# SCH_555-circuit_2025-10-19.net
KiCad netlist of a schematic drawn in EasyEDA
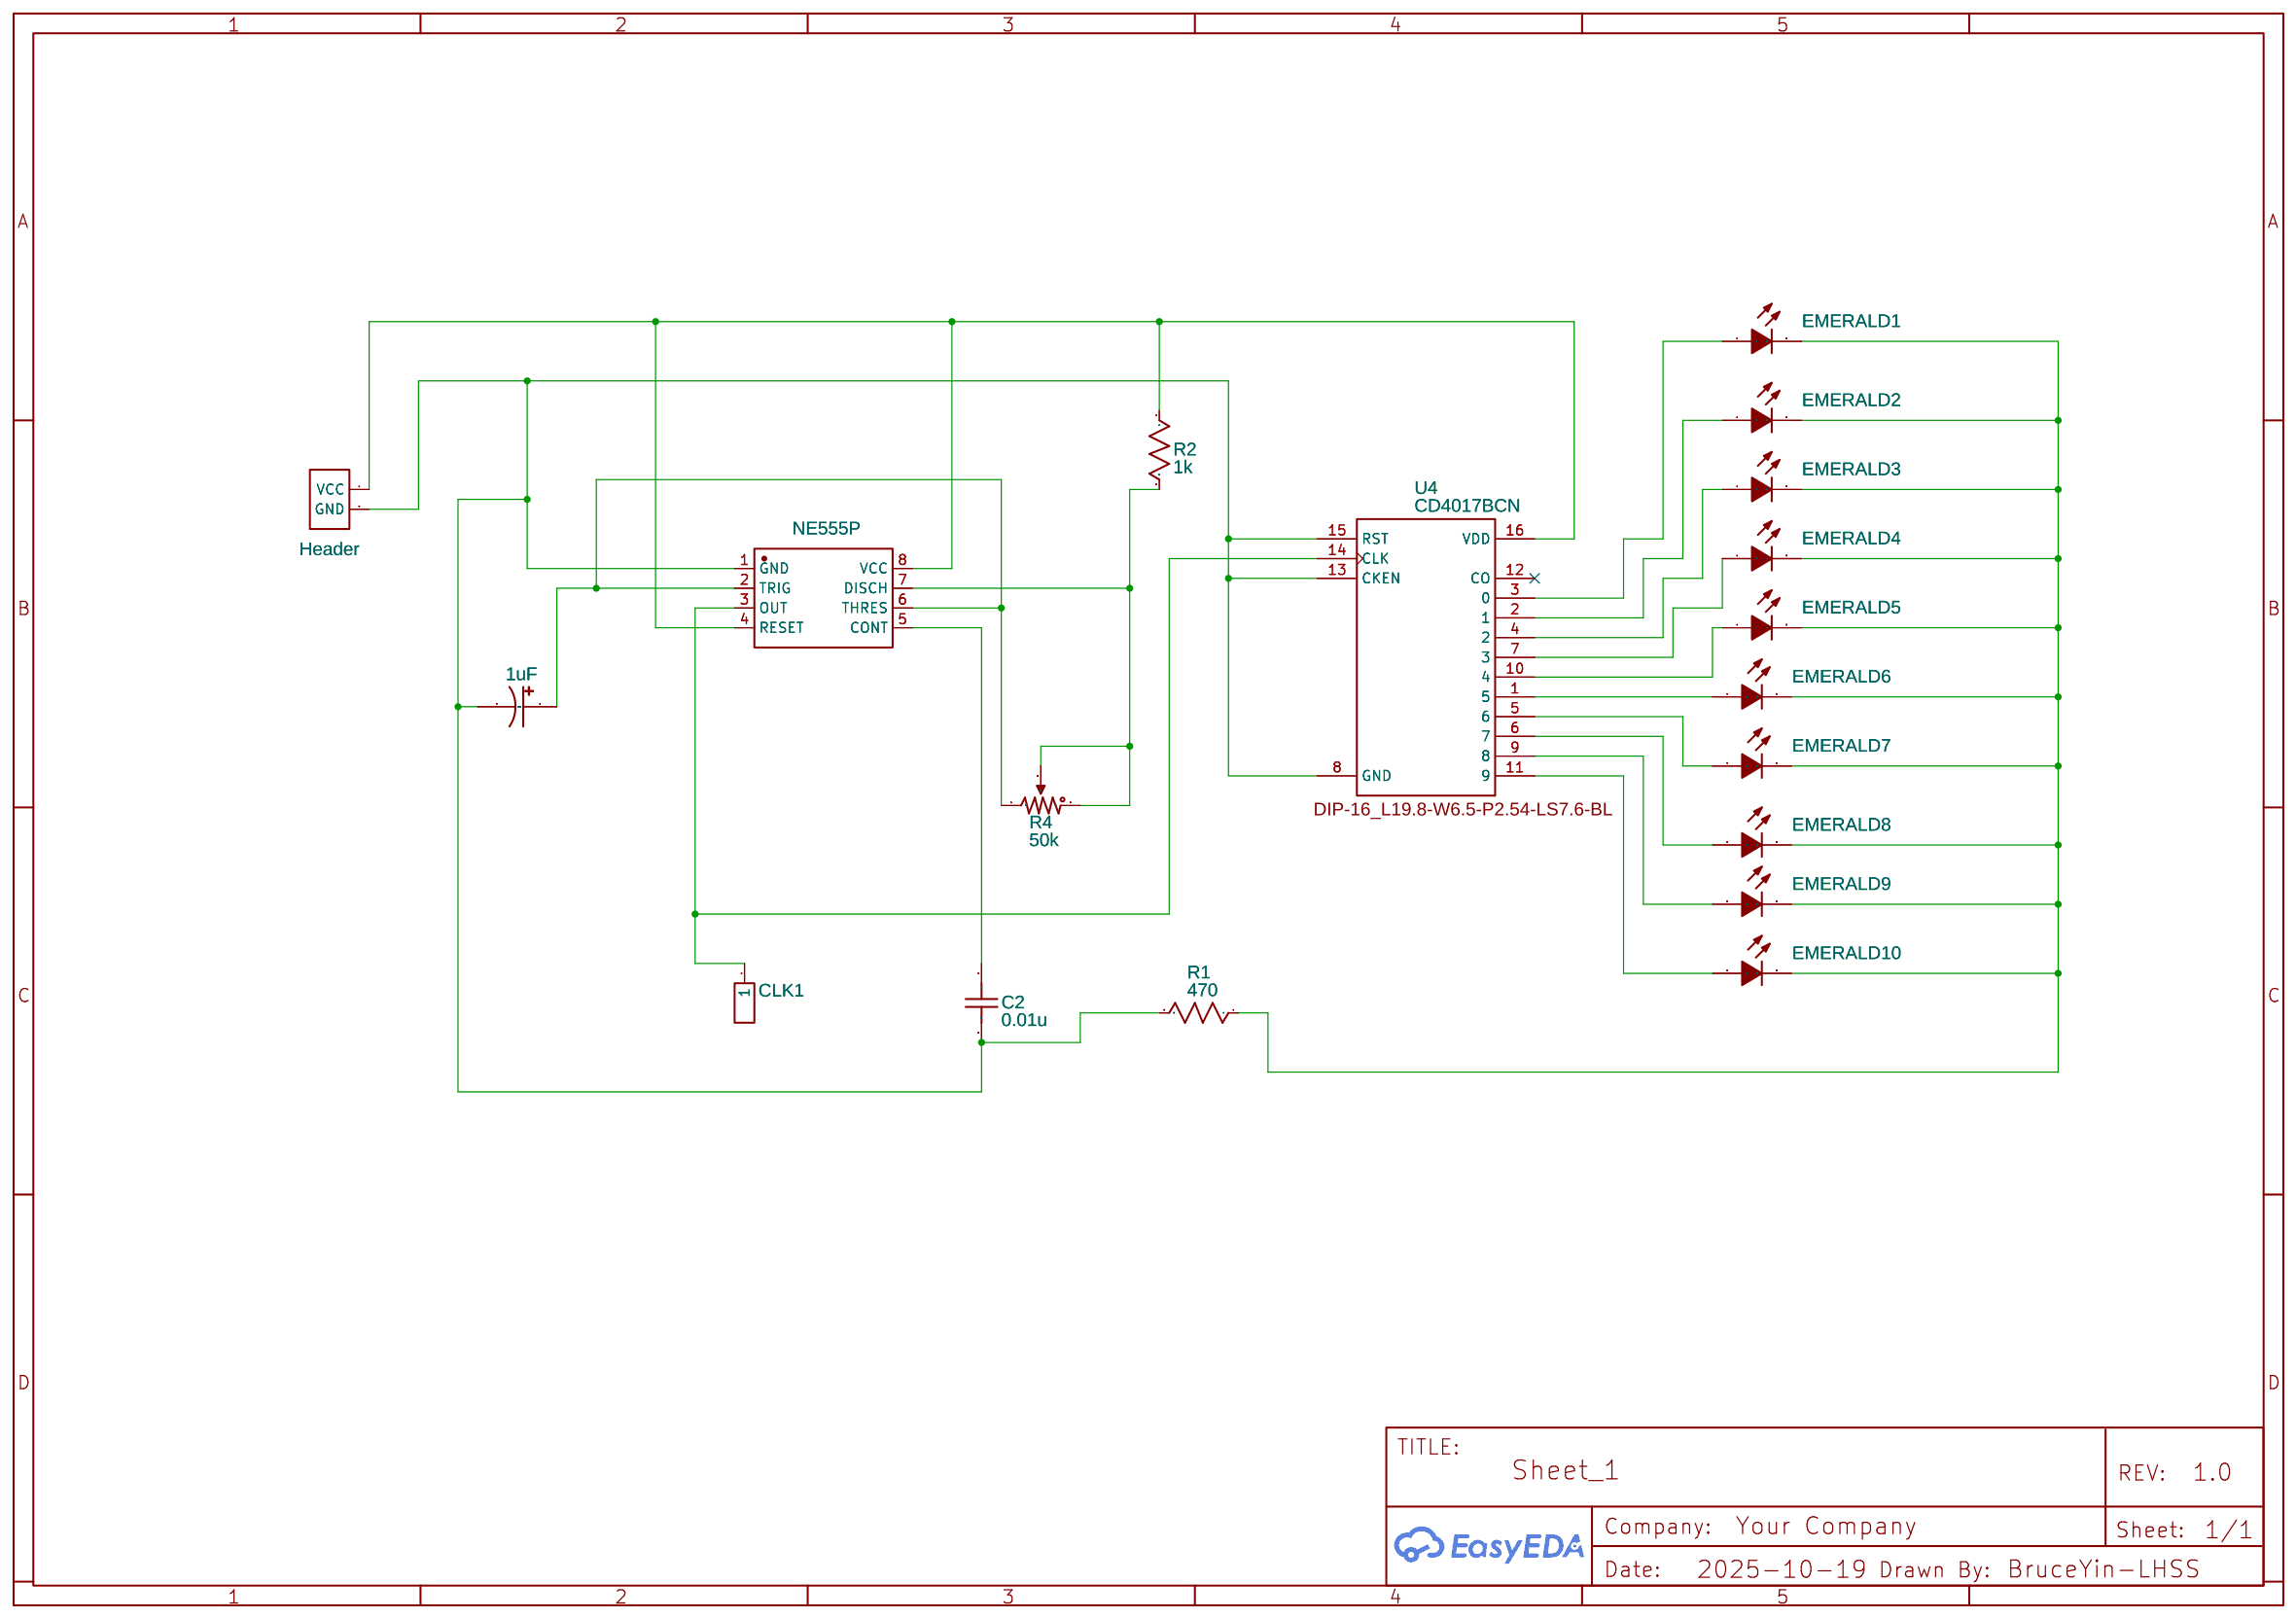
[diagram p0: schematic sheet]

(export (version "E")
  (design (tool "Eeschema 10.0.6"))
  (components
    (comp (ref "C1")
      (value "1uF")
      (fields (field (name "Manufacturer Part") "UVZ1H010MDD") (field (name "Manufacturer") "Nichicon(尼吉康)"))
      (libsource (lib "") (part "UVZ1H010MDD"))
    )
    (comp (ref "C2") (value "0.01u") (libsource (lib "") (part "C_0603_US")))
    (comp (ref "CLK1")
      (value "C81276")
      (fields
        (field (name "Manufacturer Part") "2.54-1*1P针")
        (field (name "Manufacturer") "BOOMELE(Boom Precision Elec)")
      )
      (libsource (lib "") (part "Header-Male-2.54_1x1"))
    )
    (comp (ref "EMERALD1") (value "LED_5MM") (libsource (lib "") (part "LED_5MM")))
    (comp (ref "EMERALD2") (value "LED_5MM") (libsource (lib "") (part "LED_5MM")))
    (comp (ref "EMERALD3") (value "LED_5MM") (libsource (lib "") (part "LED_5MM")))
    (comp (ref "EMERALD4") (value "LED_5MM") (libsource (lib "") (part "LED_5MM")))
    (comp (ref "EMERALD5") (value "LED_5MM") (libsource (lib "") (part "LED_5MM")))
    (comp (ref "EMERALD6") (value "LED_5MM") (libsource (lib "") (part "LED_5MM")))
    (comp (ref "EMERALD7") (value "LED_5MM") (libsource (lib "") (part "LED_5MM")))
    (comp (ref "EMERALD8") (value "LED_5MM") (libsource (lib "") (part "LED_5MM")))
    (comp (ref "EMERALD9") (value "LED_5MM") (libsource (lib "") (part "LED_5MM")))
    (comp (ref "EMERALD10") (value "LED_5MM") (libsource (lib "") (part "LED_5MM")))
    (comp (ref "H1") (value "Header") (libsource (lib "") (part "HEADER-FEMALE-2.54_1X2")))
    (comp (ref "R1")
      (value "470")
      (fields (field (name "Manufacturer Part") "?"))
      (libsource (lib "") (part "Resistor_1"))
    )
    (comp (ref "R2")
      (value "1k")
      (fields (field (name "Manufacturer Part") "?"))
      (libsource (lib "") (part "Resistor"))
    )
    (comp (ref "R4")
      (value "50k")
      (fields (field (name "Manufacturer Part") "?"))
      (libsource (lib "") (part "Potentiometer"))
    )
    (comp (ref "U2")
      (value "NE555P")
      (fields (field (name "Manufacturer") "TI(德州仪器)"))
      (libsource (lib "") (part "NE555P"))
    )
    (comp (ref "U4") (value "CD4017BCN") (libsource (lib "") (part "CD4017BCN")))
  )
  (nets
    (net (code "1") (name "Net-(EMERALD1-A)") (class "Default")
      (node (ref "EMERALD1") (pin "1") (pinfunction "A_1") (pintype "input"))
      (node (ref "U4") (pin "3") (pinfunction "0_3") (pintype "output"))
    )
    (net (code "2") (name "Net-(EMERALD1-K)") (class "Default")
      (node (ref "EMERALD1") (pin "2") (pinfunction "K_2") (pintype "input"))
      (node (ref "EMERALD10") (pin "2") (pinfunction "K_2") (pintype "input"))
      (node (ref "EMERALD2") (pin "2") (pinfunction "K_2") (pintype "input"))
      (node (ref "EMERALD3") (pin "2") (pinfunction "K_2") (pintype "input"))
      (node (ref "EMERALD4") (pin "2") (pinfunction "K_2") (pintype "input"))
      (node (ref "EMERALD5") (pin "2") (pinfunction "K_2") (pintype "input"))
      (node (ref "EMERALD6") (pin "2") (pinfunction "K_2") (pintype "input"))
      (node (ref "EMERALD7") (pin "2") (pinfunction "K_2") (pintype "input"))
      (node (ref "EMERALD8") (pin "2") (pinfunction "K_2") (pintype "input"))
      (node (ref "EMERALD9") (pin "2") (pinfunction "K_2") (pintype "input"))
      (node (ref "R1") (pin "1") (pinfunction "1_1") (pintype "unspecified"))
    )
    (net (code "3") (name "Net-(EMERALD2-A)") (class "Default")
      (node (ref "EMERALD2") (pin "1") (pinfunction "A_1") (pintype "input"))
      (node (ref "U4") (pin "2") (pinfunction "1_2") (pintype "output"))
    )
    (net (code "4") (name "Net-(EMERALD3-A)") (class "Default")
      (node (ref "EMERALD3") (pin "1") (pinfunction "A_1") (pintype "input"))
      (node (ref "U4") (pin "4") (pinfunction "2_4") (pintype "output"))
    )
    (net (code "5") (name "Net-(EMERALD4-A)") (class "Default")
      (node (ref "EMERALD4") (pin "1") (pinfunction "A_1") (pintype "input"))
      (node (ref "U4") (pin "7") (pinfunction "3_7") (pintype "output"))
    )
    (net (code "6") (name "Net-(EMERALD5-A)") (class "Default")
      (node (ref "EMERALD5") (pin "1") (pinfunction "A_1") (pintype "input"))
      (node (ref "U4") (pin "10") (pinfunction "4_10") (pintype "output"))
    )
    (net (code "7") (name "Net-(EMERALD6-A)") (class "Default")
      (node (ref "EMERALD6") (pin "1") (pinfunction "A_1") (pintype "input"))
      (node (ref "U4") (pin "1") (pinfunction "5_1") (pintype "output"))
    )
    (net (code "8") (name "Net-(EMERALD7-A)") (class "Default")
      (node (ref "EMERALD7") (pin "1") (pinfunction "A_1") (pintype "input"))
      (node (ref "U4") (pin "5") (pinfunction "6_5") (pintype "output"))
    )
    (net (code "9") (name "Net-(EMERALD8-A)") (class "Default")
      (node (ref "EMERALD8") (pin "1") (pinfunction "A_1") (pintype "input"))
      (node (ref "U4") (pin "6") (pinfunction "7_6") (pintype "output"))
    )
    (net (code "10") (name "Net-(EMERALD9-A)") (class "Default")
      (node (ref "EMERALD9") (pin "1") (pinfunction "A_1") (pintype "input"))
      (node (ref "U4") (pin "9") (pinfunction "8_9") (pintype "output"))
    )
    (net (code "11") (name "Net-(EMERALD10-A)") (class "Default")
      (node (ref "EMERALD10") (pin "1") (pinfunction "A_1") (pintype "input"))
      (node (ref "U4") (pin "11") (pinfunction "9_11") (pintype "output"))
    )
    (net (code "12") (name "Net-(H1-GND)") (class "Default")
      (node (ref "C1") (pin "2") (pinfunction "2_2") (pintype "unspecified"))
      (node (ref "C2") (pin "2") (pinfunction "2_2") (pintype "unspecified"))
      (node (ref "H1") (pin "2") (pinfunction "GND_2") (pintype "unspecified"))
      (node (ref "R1") (pin "2") (pinfunction "2_2") (pintype "unspecified"))
      (node (ref "U2") (pin "1") (pinfunction "GND_1") (pintype "unspecified"))
      (node (ref "U4") (pin "13") (pinfunction "CKEN_13") (pintype "unspecified"))
      (node (ref "U4") (pin "15") (pinfunction "RST_15") (pintype "unspecified"))
      (node (ref "U4") (pin "8") (pinfunction "GND_8") (pintype "passive"))
    )
    (net (code "13") (name "Net-(H1-VCC)") (class "Default")
      (node (ref "H1") (pin "1") (pinfunction "VCC_1") (pintype "unspecified"))
      (node (ref "R2") (pin "1") (pinfunction "1_1") (pintype "unspecified"))
      (node (ref "U2") (pin "4") (pinfunction "RESET_4") (pintype "unspecified"))
      (node (ref "U2") (pin "8") (pinfunction "VCC_8") (pintype "unspecified"))
      (node (ref "U4") (pin "16") (pinfunction "VDD_16") (pintype "passive"))
    )
    (net (code "14") (name "Net-(R4-2)") (class "Default")
      (node (ref "R2") (pin "2") (pinfunction "2_2") (pintype "unspecified"))
      (node (ref "R4") (pin "2") (pinfunction "3_2") (pintype "unspecified"))
      (node (ref "R4") (pin "3") (pinfunction "2_3") (pintype "unspecified"))
      (node (ref "U2") (pin "7") (pinfunction "DISCH_7") (pintype "unspecified"))
    )
    (net (code "15") (name "Net-(U2-CONT)") (class "Default")
      (node (ref "C2") (pin "1") (pinfunction "1_1") (pintype "unspecified"))
      (node (ref "U2") (pin "5") (pinfunction "CONT_5") (pintype "unspecified"))
    )
    (net (code "16") (name "Net-(U2-OUT)") (class "Default")
      (node (ref "CLK1") (pin "1") (pinfunction "1_1") (pintype "unspecified"))
      (node (ref "U2") (pin "3") (pinfunction "OUT_3") (pintype "unspecified"))
      (node (ref "U4") (pin "14") (pinfunction "CLK_14") (pintype "unspecified"))
    )
    (net (code "17") (name "Net-(U2-THRES)") (class "Default")
      (node (ref "C1") (pin "1") (pinfunction "1_1") (pintype "unspecified"))
      (node (ref "R4") (pin "1") (pinfunction "1_1") (pintype "unspecified"))
      (node (ref "U2") (pin "2") (pinfunction "TRIG_2") (pintype "unspecified"))
      (node (ref "U2") (pin "6") (pinfunction "THRES_6") (pintype "unspecified"))
    )
    (net (code "18") (name "unconnected-(U4-CO-Pad12)") (class "Default")
      (node (ref "U4") (pin "12") (pinfunction "CO_12") (pintype "output+no_connect"))
    )
  )
)
